# badge_flare_sample.net
KiCad netlist of a schematic drawn in EAGLE
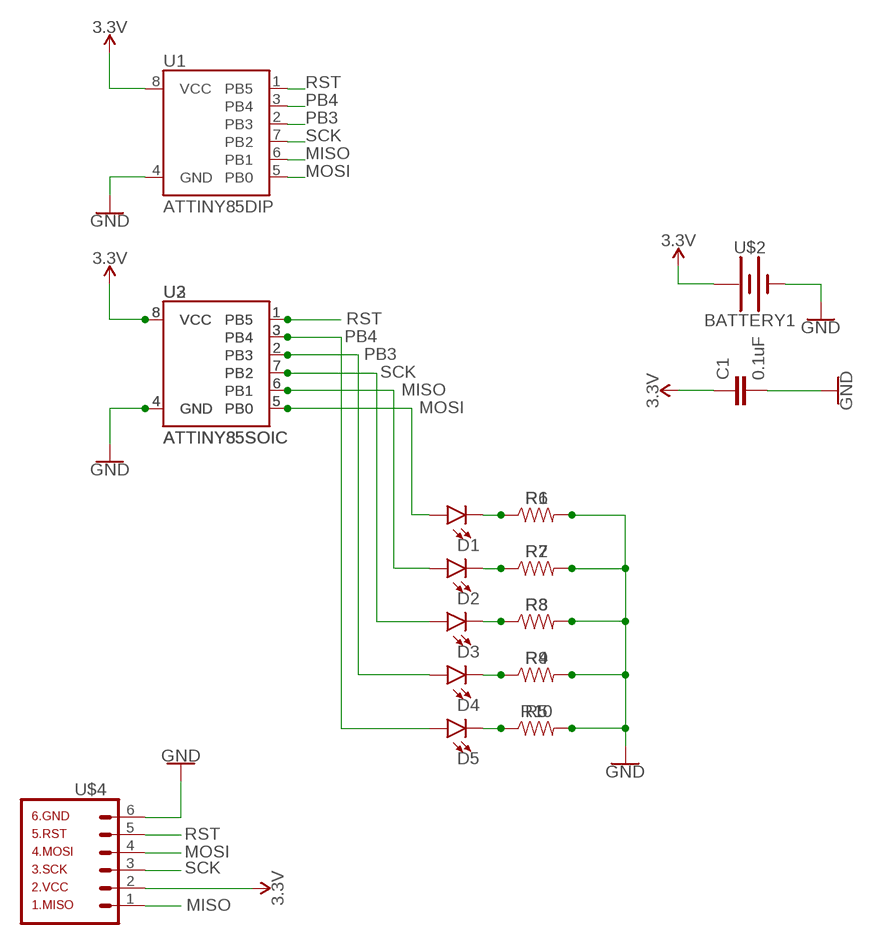
[diagram p0: schematic, sheet 1]

(export (version "E")
  (design (tool "Eeschema 10.0.6"))
  (components
    (comp (ref "C1")
      (value "0.1uF")
      (footprint "eagle-import:CAP-PTH-SMALL-KIT")
      (libsource (lib "eagle-import") (part "0.1UF-KIT-EZ-50V-20%"))
    )
    (comp (ref "D1")
      (value "LED5MM")
      (footprint "eagle-import:LED_5MM")
      (libsource (lib "eagle-import") (part "LED5MM"))
    )
    (comp (ref "D2")
      (value "LED5MM")
      (footprint "eagle-import:LED_5MM")
      (libsource (lib "eagle-import") (part "LED5MM"))
    )
    (comp (ref "D3")
      (value "LED5MM")
      (footprint "eagle-import:LED_5MM")
      (libsource (lib "eagle-import") (part "LED5MM"))
    )
    (comp (ref "D4")
      (value "LED5MM")
      (footprint "eagle-import:LED_5MM")
      (libsource (lib "eagle-import") (part "LED5MM"))
    )
    (comp (ref "D5")
      (value "LED5MM")
      (footprint "eagle-import:LED_5MM")
      (libsource (lib "eagle-import") (part "LED5MM"))
    )
    (comp (ref "R1")
      (value "RESISTORAXIAL-0.3")
      (footprint "eagle-import:AXIAL-0.3")
      (libsource (lib "eagle-import") (part "RESISTORAXIAL-0.3"))
    )
    (comp (ref "R2")
      (value "RESISTORAXIAL-0.3")
      (footprint "eagle-import:AXIAL-0.3")
      (libsource (lib "eagle-import") (part "RESISTORAXIAL-0.3"))
    )
    (comp (ref "R3")
      (value "RESISTORAXIAL-0.3")
      (footprint "eagle-import:AXIAL-0.3")
      (libsource (lib "eagle-import") (part "RESISTORAXIAL-0.3"))
    )
    (comp (ref "R4")
      (value "RESISTORAXIAL-0.3")
      (footprint "eagle-import:AXIAL-0.3")
      (libsource (lib "eagle-import") (part "RESISTORAXIAL-0.3"))
    )
    (comp (ref "R5")
      (value "RESISTORAXIAL-0.3")
      (footprint "eagle-import:AXIAL-0.3")
      (libsource (lib "eagle-import") (part "RESISTORAXIAL-0.3"))
    )
    (comp (ref "R6")
      (value "RESISTOR0805")
      (footprint "eagle-import:0805")
      (libsource (lib "eagle-import") (part "RESISTOR0805"))
    )
    (comp (ref "R7")
      (value "RESISTOR0805")
      (footprint "eagle-import:0805")
      (libsource (lib "eagle-import") (part "RESISTOR0805"))
    )
    (comp (ref "R8")
      (value "RESISTOR0805")
      (footprint "eagle-import:0805")
      (libsource (lib "eagle-import") (part "RESISTOR0805"))
    )
    (comp (ref "R9")
      (value "RESISTOR0805")
      (footprint "eagle-import:0805")
      (libsource (lib "eagle-import") (part "RESISTOR0805"))
    )
    (comp (ref "R10")
      (value "RESISTOR0805")
      (footprint "eagle-import:0805")
      (libsource (lib "eagle-import") (part "RESISTOR0805"))
    )
    (comp (ref "U$2")
      (value "BATTERY1")
      (footprint "eagle-import:BATTERY_HOLDER_COIN")
      (libsource (lib "eagle-import") (part "BATTERY1"))
    )
    (comp (ref "U$4")
      (value "ISP_PROGRAMMER_3MM_PITCH")
      (footprint "eagle-import:1X06-1.27MM-3MM_PITCH_PROGRAMMER")
      (libsource (lib "eagle-import") (part "ISP_PROGRAMMER_3MM_PITCH"))
    )
    (comp (ref "U1")
      (value "ATTINY85DIP")
      (footprint "eagle-import:DIP08")
      (libsource (lib "eagle-import") (part "ATTINY85DIP"))
    )
    (comp (ref "U2")
      (value "ATTINY85SOIC")
      (footprint "eagle-import:ATTINY85")
      (libsource (lib "eagle-import") (part "ATTINY85SOIC"))
    )
    (comp (ref "U3")
      (value "ATTINY85SOIC")
      (footprint "eagle-import:ATTINY85")
      (libsource (lib "eagle-import") (part "ATTINY85SOIC"))
    )
  )
  (nets
    (net (code "1") (name "/MISO") (class "Default")
      (node (ref "D2") (pin "A") (pinfunction "A_A") (pintype "passive"))
      (node (ref "U$4") (pin "1") (pinfunction "MISO_1") (pintype "passive"))
      (node (ref "U1") (pin "6") (pinfunction "PB1_6") (pintype "bidirectional"))
      (node (ref "U2") (pin "6") (pinfunction "PB1_6") (pintype "bidirectional"))
      (node (ref "U3") (pin "6") (pinfunction "PB1_6") (pintype "bidirectional"))
    )
    (net (code "2") (name "/MOSI") (class "Default")
      (node (ref "D1") (pin "A") (pinfunction "A_A") (pintype "passive"))
      (node (ref "U$4") (pin "4") (pinfunction "MOSI_4") (pintype "passive"))
      (node (ref "U1") (pin "5") (pinfunction "PB0_5") (pintype "bidirectional"))
      (node (ref "U2") (pin "5") (pinfunction "PB0_5") (pintype "bidirectional"))
      (node (ref "U3") (pin "5") (pinfunction "PB0_5") (pintype "bidirectional"))
    )
    (net (code "3") (name "/PB3") (class "Default")
      (node (ref "D4") (pin "A") (pinfunction "A_A") (pintype "passive"))
      (node (ref "U1") (pin "2") (pinfunction "PB3_2") (pintype "bidirectional"))
      (node (ref "U2") (pin "2") (pinfunction "PB3_2") (pintype "bidirectional"))
      (node (ref "U3") (pin "2") (pinfunction "PB3_2") (pintype "bidirectional"))
    )
    (net (code "4") (name "/PB4") (class "Default")
      (node (ref "D5") (pin "A") (pinfunction "A_A") (pintype "passive"))
      (node (ref "U1") (pin "3") (pinfunction "PB4_3") (pintype "bidirectional"))
      (node (ref "U2") (pin "3") (pinfunction "PB4_3") (pintype "bidirectional"))
      (node (ref "U3") (pin "3") (pinfunction "PB4_3") (pintype "bidirectional"))
    )
    (net (code "5") (name "/RST") (class "Default")
      (node (ref "U$4") (pin "5") (pinfunction "RST_5") (pintype "passive"))
      (node (ref "U1") (pin "1") (pinfunction "PB5_1") (pintype "bidirectional"))
      (node (ref "U2") (pin "1") (pinfunction "PB5_1") (pintype "bidirectional"))
      (node (ref "U3") (pin "1") (pinfunction "PB5_1") (pintype "bidirectional"))
    )
    (net (code "6") (name "/SCK") (class "Default")
      (node (ref "D3") (pin "A") (pinfunction "A_A") (pintype "passive"))
      (node (ref "U$4") (pin "3") (pinfunction "SCK_3") (pintype "passive"))
      (node (ref "U1") (pin "7") (pinfunction "PB2_7") (pintype "bidirectional"))
      (node (ref "U2") (pin "7") (pinfunction "PB2_7") (pintype "bidirectional"))
      (node (ref "U3") (pin "7") (pinfunction "PB2_7") (pintype "bidirectional"))
    )
    (net (code "7") (name "3.3V") (class "Default")
      (node (ref "C1") (pin "1") (pinfunction "1_1") (pintype "passive"))
      (node (ref "U$2") (pin "1") (pinfunction "+_1") (pintype "power_in"))
      (node (ref "U$4") (pin "2") (pinfunction "VCC_2") (pintype "passive"))
      (node (ref "U1") (pin "8") (pinfunction "VCC_8") (pintype "bidirectional"))
      (node (ref "U2") (pin "8") (pinfunction "VCC_8") (pintype "bidirectional"))
      (node (ref "U3") (pin "8") (pinfunction "VCC_8") (pintype "bidirectional"))
    )
    (net (code "8") (name "GND") (class "Default")
      (node (ref "C1") (pin "2") (pinfunction "2_2") (pintype "passive"))
      (node (ref "R1") (pin "P$2") (pinfunction "2_P$2") (pintype "passive"))
      (node (ref "R10") (pin "2") (pinfunction "2_2") (pintype "passive"))
      (node (ref "R2") (pin "P$2") (pinfunction "2_P$2") (pintype "passive"))
      (node (ref "R3") (pin "P$2") (pinfunction "2_P$2") (pintype "passive"))
      (node (ref "R4") (pin "P$2") (pinfunction "2_P$2") (pintype "passive"))
      (node (ref "R5") (pin "P$2") (pinfunction "2_P$2") (pintype "passive"))
      (node (ref "R6") (pin "2") (pinfunction "2_2") (pintype "passive"))
      (node (ref "R7") (pin "2") (pinfunction "2_2") (pintype "passive"))
      (node (ref "R8") (pin "2") (pinfunction "2_2") (pintype "passive"))
      (node (ref "R9") (pin "2") (pinfunction "2_2") (pintype "passive"))
      (node (ref "U$2") (pin "2") (pinfunction "-_2") (pintype "power_in"))
      (node (ref "U$4") (pin "6") (pinfunction "GND_6") (pintype "passive"))
      (node (ref "U1") (pin "4") (pinfunction "GND_4") (pintype "bidirectional"))
      (node (ref "U2") (pin "4") (pinfunction "GND_4") (pintype "bidirectional"))
      (node (ref "U3") (pin "4") (pinfunction "GND_4") (pintype "bidirectional"))
    )
    (net (code "9") (name "Net-(D1-C)") (class "Default")
      (node (ref "D1") (pin "K") (pinfunction "C_K") (pintype "passive"))
      (node (ref "R1") (pin "P$1") (pinfunction "1_P$1") (pintype "passive"))
      (node (ref "R6") (pin "1") (pinfunction "1_1") (pintype "passive"))
    )
    (net (code "10") (name "Net-(D2-C)") (class "Default")
      (node (ref "D2") (pin "K") (pinfunction "C_K") (pintype "passive"))
      (node (ref "R2") (pin "P$1") (pinfunction "1_P$1") (pintype "passive"))
      (node (ref "R7") (pin "1") (pinfunction "1_1") (pintype "passive"))
    )
    (net (code "11") (name "Net-(D3-C)") (class "Default")
      (node (ref "D3") (pin "K") (pinfunction "C_K") (pintype "passive"))
      (node (ref "R3") (pin "P$1") (pinfunction "1_P$1") (pintype "passive"))
      (node (ref "R8") (pin "1") (pinfunction "1_1") (pintype "passive"))
    )
    (net (code "12") (name "Net-(D4-C)") (class "Default")
      (node (ref "D4") (pin "K") (pinfunction "C_K") (pintype "passive"))
      (node (ref "R4") (pin "P$1") (pinfunction "1_P$1") (pintype "passive"))
      (node (ref "R9") (pin "1") (pinfunction "1_1") (pintype "passive"))
    )
    (net (code "13") (name "Net-(D5-C)") (class "Default")
      (node (ref "D5") (pin "K") (pinfunction "C_K") (pintype "passive"))
      (node (ref "R10") (pin "1") (pinfunction "1_1") (pintype "passive"))
      (node (ref "R5") (pin "P$1") (pinfunction "1_P$1") (pintype "passive"))
    )
  )
)
